# STM32F405RGT6.net
KiCad netlist of a schematic drawn in Altium Designer
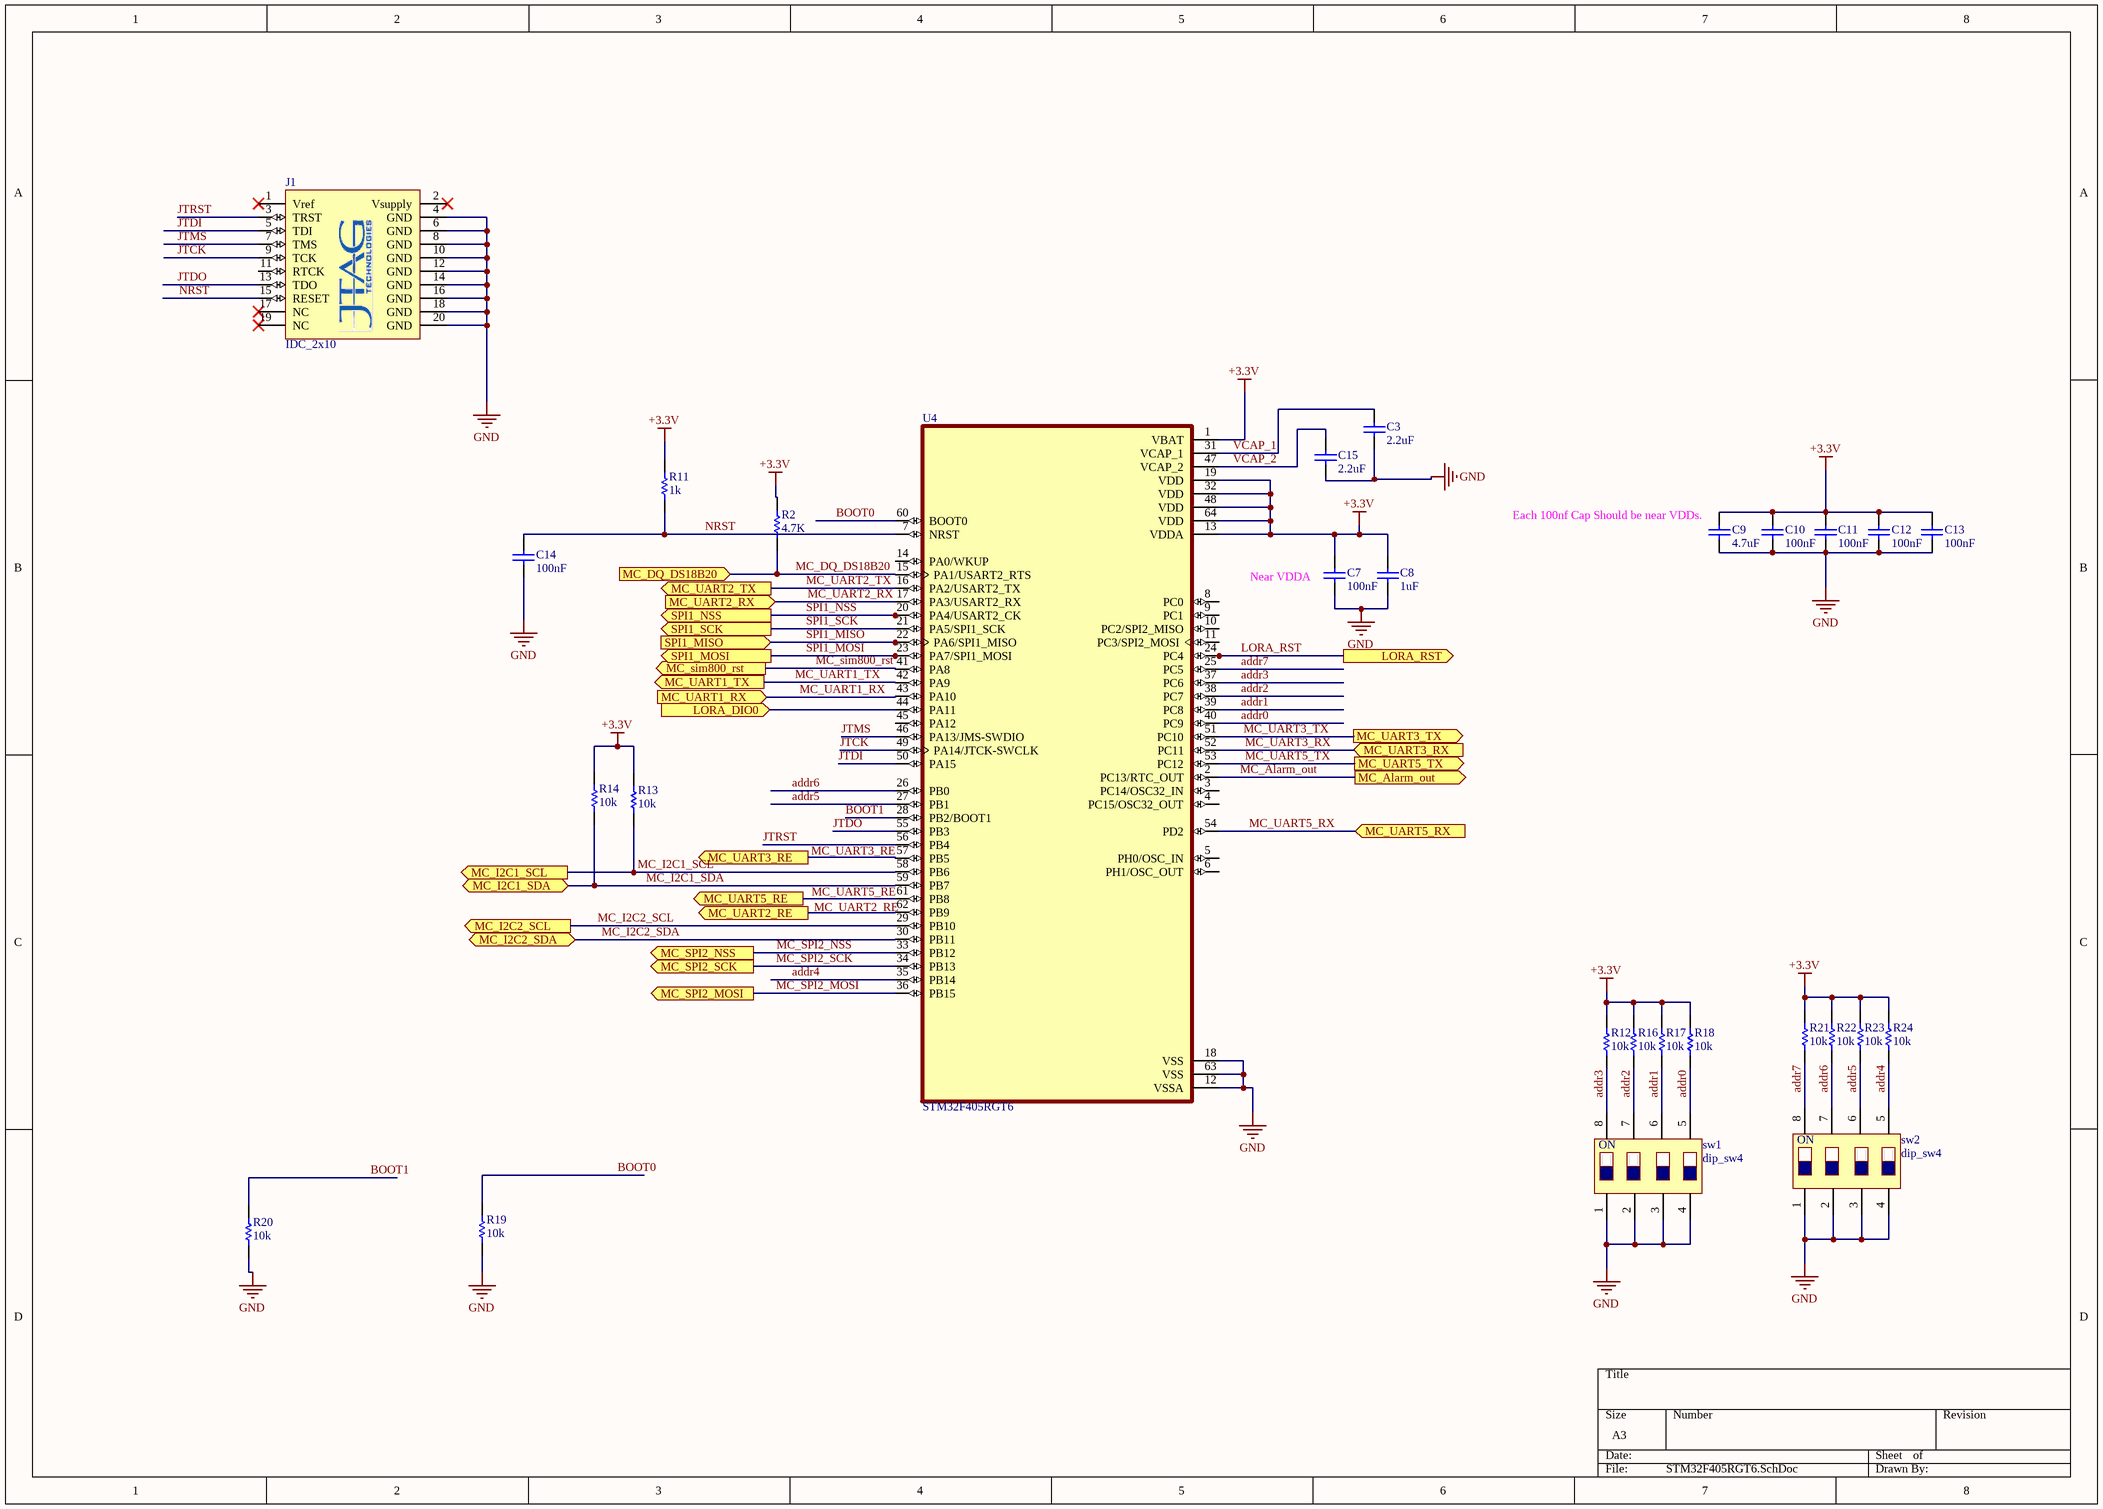
[diagram p0: STM32F405RGT6.SchDoc]

(export (version "E")
  (design (tool "Eeschema 10.0.6"))
  (components
    (comp (ref "C3")
      (value "2.2uF")
      (footprint "C-805")
      (description "Capacitor")
      (fields (field (name "Comment") "C-805") (field (name "PUBLISHER") "Altium Limited"))
      (libsource (lib "AfraLIB") (part "C-805"))
    )
    (comp (ref "C7")
      (value "100nF")
      (footprint "C-805")
      (description "Capacitor")
      (fields (field (name "Comment") "C-805") (field (name "PUBLISHER") "Altium Limited"))
      (libsource (lib "AfraLIB") (part "C-805"))
    )
    (comp (ref "C8")
      (value "1uF")
      (footprint "C-805")
      (description "Capacitor")
      (fields (field (name "Comment") "C-805") (field (name "PUBLISHER") "Altium Limited"))
      (libsource (lib "AfraLIB") (part "C-805"))
    )
    (comp (ref "C9")
      (value "4.7uF")
      (footprint "C-1206")
      (description "Capacitor")
      (fields (field (name "Comment") "C-1206") (field (name "PUBLISHER") "Altium Limited"))
      (libsource (lib "AfraLIB") (part "C-1206"))
    )
    (comp (ref "C10")
      (value "100nF")
      (footprint "C-603")
      (description "Capacitor")
      (fields (field (name "Comment") "C-603") (field (name "PUBLISHER") "Altium Limited"))
      (libsource (lib "AfraLIB") (part "C-603"))
    )
    (comp (ref "C11")
      (value "100nF")
      (footprint "C-603")
      (description "Capacitor")
      (fields (field (name "Comment") "C-603") (field (name "PUBLISHER") "Altium Limited"))
      (libsource (lib "AfraLIB") (part "C-603"))
    )
    (comp (ref "C12")
      (value "100nF")
      (footprint "C-603")
      (description "Capacitor")
      (fields (field (name "Comment") "C-603") (field (name "PUBLISHER") "Altium Limited"))
      (libsource (lib "AfraLIB") (part "C-603"))
    )
    (comp (ref "C13")
      (value "100nF")
      (footprint "C-603")
      (description "Capacitor")
      (fields (field (name "Comment") "C-603") (field (name "PUBLISHER") "Altium Limited"))
      (libsource (lib "AfraLIB") (part "C-603"))
    )
    (comp (ref "C14")
      (value "100nF")
      (footprint "C-805")
      (description "Capacitor")
      (fields (field (name "Comment") "C-805") (field (name "PUBLISHER") "Altium Limited"))
      (libsource (lib "AfraLIB") (part "C-805"))
    )
    (comp (ref "C15")
      (value "2.2uF")
      (footprint "C-805")
      (description "Capacitor")
      (fields (field (name "Comment") "C-805") (field (name "PUBLISHER") "Altium Limited"))
      (libsource (lib "AfraLIB") (part "C-805"))
    )
    (comp (ref "J1")
      (value "IDC_2x10")
      (footprint "IDC2.54-V20D")
      (description "20 Pin Standard JTAG Header For ARM JLINK")
      (fields (field (name "DESIGNER") "Eng. Saeid Jorablo") (field (name "PUBLISHER") "SJ UnLimited"))
      (libsource (lib "AfraLIB") (part "JTAG_JLINK"))
    )
    (comp (ref "R2")
      (value "4.7K")
      (footprint "R-805")
      (description "Resistor")
      (fields (field (name "Comment") "R-805"))
      (libsource (lib "AfraLIB") (part "R-805"))
    )
    (comp (ref "R11")
      (value "1k")
      (footprint "R-805")
      (description "Resistor")
      (fields (field (name "Comment") "R-805"))
      (libsource (lib "AfraLIB") (part "R-805"))
    )
    (comp (ref "R12")
      (value "10k")
      (footprint "R-805")
      (description "Resistor")
      (fields (field (name "Comment") "R-805"))
      (libsource (lib "AfraLIB") (part "R-805"))
    )
    (comp (ref "R13")
      (value "10k")
      (footprint "R-805")
      (description "Resistor")
      (fields (field (name "Comment") "R-805"))
      (libsource (lib "AfraLIB") (part "R-805"))
    )
    (comp (ref "R14")
      (value "10k")
      (footprint "R-805")
      (description "Resistor")
      (fields (field (name "Comment") "R-805"))
      (libsource (lib "AfraLIB") (part "R-805"))
    )
    (comp (ref "R16")
      (value "10k")
      (footprint "R-805")
      (description "Resistor")
      (fields (field (name "Comment") "R-805"))
      (libsource (lib "AfraLIB") (part "R-805"))
    )
    (comp (ref "R17")
      (value "10k")
      (footprint "R-805")
      (description "Resistor")
      (fields (field (name "Comment") "R-805"))
      (libsource (lib "AfraLIB") (part "R-805"))
    )
    (comp (ref "R18")
      (value "10k")
      (footprint "R-805")
      (description "Resistor")
      (fields (field (name "Comment") "R-805"))
      (libsource (lib "AfraLIB") (part "R-805"))
    )
    (comp (ref "R19")
      (value "10k")
      (footprint "R-805")
      (description "Resistor")
      (fields (field (name "Comment") "R-805"))
      (libsource (lib "AfraLIB") (part "R-805"))
    )
    (comp (ref "R20")
      (value "10k")
      (footprint "R-805")
      (description "Resistor")
      (fields (field (name "Comment") "R-805"))
      (libsource (lib "AfraLIB") (part "R-805"))
    )
    (comp (ref "R21")
      (value "10k")
      (footprint "R-805")
      (description "Resistor")
      (fields (field (name "Comment") "R-805"))
      (libsource (lib "AfraLIB") (part "R-805"))
    )
    (comp (ref "R22")
      (value "10k")
      (footprint "R-805")
      (description "Resistor")
      (fields (field (name "Comment") "R-805"))
      (libsource (lib "AfraLIB") (part "R-805"))
    )
    (comp (ref "R23")
      (value "10k")
      (footprint "R-805")
      (description "Resistor")
      (fields (field (name "Comment") "R-805"))
      (libsource (lib "AfraLIB") (part "R-805"))
    )
    (comp (ref "R24")
      (value "10k")
      (footprint "R-805")
      (description "Resistor")
      (fields (field (name "Comment") "R-805"))
      (libsource (lib "AfraLIB") (part "R-805"))
    )
    (comp (ref "sw1")
      (value "dip_sw4")
      (footprint "dipSW_4")
      (description "dip switch, 4-Pin")
      (fields (field (name "PUBLISHER") "Altium Limited"))
      (libsource (lib "AfraLIB") (part "dip_sw4"))
    )
    (comp (ref "sw2")
      (value "dip_sw4")
      (footprint "dipSW_4")
      (description "dip switch, 4-Pin")
      (fields (field (name "PUBLISHER") "Altium Limited"))
      (libsource (lib "AfraLIB") (part "dip_sw4"))
    )
    (comp (ref "U4")
      (value "STM32F405RGT6")
      (footprint "stm32f405rgt6")
      (description "ARMÂ® CortexÂ®-M4 STM32F4 Microcontroller IC 32-Bit 168MHz 1MB _1M x 8_ FLASH 64-LQFP _10x10_")
      (fields (field (name "MF") "STMicroelectronics") (field (name "DIGI-KEY_PART_NUMBER") "497-11767-ND"))
      (libsource (lib "AfraLIB") (part "STM32F405RGT6"))
    )
  )
  (nets
    (net (code "1") (name "+3.3V") (class "Default")
      (node (ref "C10") (pin "1") (pinfunction "1_1") (pintype "passive"))
      (node (ref "C11") (pin "1") (pinfunction "1_1") (pintype "passive"))
      (node (ref "C12") (pin "1") (pinfunction "1_1") (pintype "passive"))
      (node (ref "C13") (pin "1") (pinfunction "1_1") (pintype "passive"))
      (node (ref "C7") (pin "1") (pinfunction "1_1") (pintype "passive"))
      (node (ref "C8") (pin "2") (pinfunction "2_2") (pintype "passive"))
      (node (ref "C9") (pin "2") (pinfunction "2_2") (pintype "passive"))
      (node (ref "R11") (pin "2") (pinfunction "2_2") (pintype "passive"))
      (node (ref "R12") (pin "2") (pinfunction "2_2") (pintype "passive"))
      (node (ref "R13") (pin "2") (pinfunction "2_2") (pintype "passive"))
      (node (ref "R14") (pin "2") (pinfunction "2_2") (pintype "passive"))
      (node (ref "R16") (pin "2") (pinfunction "2_2") (pintype "passive"))
      (node (ref "R17") (pin "2") (pinfunction "2_2") (pintype "passive"))
      (node (ref "R18") (pin "2") (pinfunction "2_2") (pintype "passive"))
      (node (ref "R2") (pin "2") (pinfunction "2_2") (pintype "passive"))
      (node (ref "R21") (pin "2") (pinfunction "2_2") (pintype "passive"))
      (node (ref "R22") (pin "2") (pinfunction "2_2") (pintype "passive"))
      (node (ref "R23") (pin "2") (pinfunction "2_2") (pintype "passive"))
      (node (ref "R24") (pin "2") (pinfunction "2_2") (pintype "passive"))
      (node (ref "U4") (pin "1") (pinfunction "VBAT_1") (pintype "power_in"))
      (node (ref "U4") (pin "13") (pinfunction "VDDA_13") (pintype "power_in"))
      (node (ref "U4") (pin "19") (pinfunction "VDD_19") (pintype "power_in"))
      (node (ref "U4") (pin "32") (pinfunction "VDD_32") (pintype "power_in"))
      (node (ref "U4") (pin "48") (pinfunction "VDD_48") (pintype "power_in"))
      (node (ref "U4") (pin "64") (pinfunction "VDD_64") (pintype "power_in"))
    )
    (net (code "2") (name "/BOOT0") (class "Default")
      (node (ref "R19") (pin "2") (pinfunction "2_2") (pintype "passive"))
      (node (ref "U4") (pin "60") (pinfunction "BOOT0_60") (pintype "bidirectional"))
    )
    (net (code "3") (name "/BOOT1") (class "Default")
      (node (ref "R20") (pin "1") (pinfunction "1_1") (pintype "passive"))
      (node (ref "U4") (pin "28") (pinfunction "PB2/BOOT1_28") (pintype "bidirectional"))
    )
    (net (code "4") (name "/JTCK") (class "Default")
      (node (ref "J1") (pin "9") (pinfunction "TCK_9") (pintype "bidirectional"))
      (node (ref "U4") (pin "49") (pinfunction "PA14/JTCK-SWCLK_49") (pintype "bidirectional"))
    )
    (net (code "5") (name "/JTDI") (class "Default")
      (node (ref "J1") (pin "5") (pinfunction "TDI_5") (pintype "bidirectional"))
      (node (ref "U4") (pin "50") (pinfunction "PA15_50") (pintype "bidirectional"))
    )
    (net (code "6") (name "/JTDO") (class "Default")
      (node (ref "J1") (pin "13") (pinfunction "TDO_13") (pintype "bidirectional"))
      (node (ref "U4") (pin "55") (pinfunction "PB3_55") (pintype "bidirectional"))
    )
    (net (code "7") (name "/JTMS") (class "Default")
      (node (ref "J1") (pin "7") (pinfunction "TMS_7") (pintype "bidirectional"))
      (node (ref "U4") (pin "46") (pinfunction "PA13/JMS-SWDIO_46") (pintype "bidirectional"))
    )
    (net (code "8") (name "/JTRST") (class "Default")
      (node (ref "J1") (pin "3") (pinfunction "TRST_3") (pintype "bidirectional"))
      (node (ref "U4") (pin "56") (pinfunction "PB4_56") (pintype "bidirectional"))
    )
    (net (code "9") (name "/LORA_DIO0") (class "Default")
      (node (ref "U4") (pin "44") (pinfunction "PA11_44") (pintype "bidirectional"))
    )
    (net (code "10") (name "/LORA_RST") (class "Default")
      (node (ref "U4") (pin "24") (pinfunction "PC4_24") (pintype "bidirectional"))
    )
    (net (code "11") (name "/MC_Alarm_out") (class "Default")
      (node (ref "U4") (pin "2") (pinfunction "PC13/RTC_OUT_2") (pintype "bidirectional"))
    )
    (net (code "12") (name "/MC_DQ_DS18B20") (class "Default")
      (node (ref "R2") (pin "1") (pinfunction "1_1") (pintype "passive"))
      (node (ref "U4") (pin "15") (pinfunction "PA1/USART2_RTS_15") (pintype "bidirectional"))
    )
    (net (code "13") (name "/MC_I2C1_SCL") (class "Default")
      (node (ref "R13") (pin "1") (pinfunction "1_1") (pintype "passive"))
      (node (ref "U4") (pin "58") (pinfunction "PB6_58") (pintype "bidirectional"))
    )
    (net (code "14") (name "/MC_I2C1_SDA") (class "Default")
      (node (ref "R14") (pin "1") (pinfunction "1_1") (pintype "passive"))
      (node (ref "U4") (pin "59") (pinfunction "PB7_59") (pintype "bidirectional"))
    )
    (net (code "15") (name "/MC_I2C2_SCL") (class "Default")
      (node (ref "U4") (pin "29") (pinfunction "PB10_29") (pintype "bidirectional"))
    )
    (net (code "16") (name "/MC_I2C2_SDA") (class "Default")
      (node (ref "U4") (pin "30") (pinfunction "PB11_30") (pintype "bidirectional"))
    )
    (net (code "17") (name "/MC_SPI2_MOSI") (class "Default")
      (node (ref "U4") (pin "36") (pinfunction "PB15_36") (pintype "bidirectional"))
    )
    (net (code "18") (name "/MC_SPI2_NSS") (class "Default")
      (node (ref "U4") (pin "33") (pinfunction "PB12_33") (pintype "bidirectional"))
    )
    (net (code "19") (name "/MC_SPI2_SCK") (class "Default")
      (node (ref "U4") (pin "34") (pinfunction "PB13_34") (pintype "bidirectional"))
    )
    (net (code "20") (name "/MC_UART1_RX") (class "Default")
      (node (ref "U4") (pin "43") (pinfunction "PA10_43") (pintype "bidirectional"))
    )
    (net (code "21") (name "/MC_UART1_TX") (class "Default")
      (node (ref "U4") (pin "42") (pinfunction "PA9_42") (pintype "bidirectional"))
    )
    (net (code "22") (name "/MC_UART2_RE") (class "Default")
      (node (ref "U4") (pin "62") (pinfunction "PB9_62") (pintype "bidirectional"))
    )
    (net (code "23") (name "/MC_UART2_RX") (class "Default")
      (node (ref "U4") (pin "17") (pinfunction "PA3/USART2_RX_17") (pintype "bidirectional"))
    )
    (net (code "24") (name "/MC_UART2_TX") (class "Default")
      (node (ref "U4") (pin "16") (pinfunction "PA2/USART2_TX_16") (pintype "bidirectional"))
    )
    (net (code "25") (name "/MC_UART3_RE") (class "Default")
      (node (ref "U4") (pin "57") (pinfunction "PB5_57") (pintype "bidirectional"))
    )
    (net (code "26") (name "/MC_UART3_RX") (class "Default")
      (node (ref "U4") (pin "52") (pinfunction "PC11_52") (pintype "bidirectional"))
    )
    (net (code "27") (name "/MC_UART3_TX") (class "Default")
      (node (ref "U4") (pin "51") (pinfunction "PC10_51") (pintype "bidirectional"))
    )
    (net (code "28") (name "/MC_UART5_RE") (class "Default")
      (node (ref "U4") (pin "61") (pinfunction "PB8_61") (pintype "bidirectional"))
    )
    (net (code "29") (name "/MC_UART5_RX") (class "Default")
      (node (ref "U4") (pin "54") (pinfunction "PD2_54") (pintype "bidirectional"))
    )
    (net (code "30") (name "/MC_UART5_TX") (class "Default")
      (node (ref "U4") (pin "53") (pinfunction "PC12_53") (pintype "bidirectional"))
    )
    (net (code "31") (name "/MC_sim800_rst") (class "Default")
      (node (ref "U4") (pin "41") (pinfunction "PA8_41") (pintype "bidirectional"))
    )
    (net (code "32") (name "/NRST") (class "Default")
      (node (ref "C14") (pin "1") (pinfunction "1_1") (pintype "passive"))
      (node (ref "J1") (pin "15") (pinfunction "RESET_15") (pintype "bidirectional"))
      (node (ref "R11") (pin "1") (pinfunction "1_1") (pintype "passive"))
      (node (ref "U4") (pin "7") (pinfunction "NRST_7") (pintype "bidirectional"))
    )
    (net (code "33") (name "/SPI1_MISO") (class "Default")
      (node (ref "U4") (pin "22") (pinfunction "PA6/SPI1_MISO_22") (pintype "bidirectional"))
    )
    (net (code "34") (name "/SPI1_MOSI") (class "Default")
      (node (ref "U4") (pin "23") (pinfunction "PA7/SPI1_MOSI_23") (pintype "bidirectional"))
    )
    (net (code "35") (name "/SPI1_NSS") (class "Default")
      (node (ref "U4") (pin "20") (pinfunction "PA4/USART2_CK_20") (pintype "bidirectional"))
    )
    (net (code "36") (name "/SPI1_SCK") (class "Default")
      (node (ref "U4") (pin "21") (pinfunction "PA5/SPI1_SCK_21") (pintype "bidirectional"))
    )
    (net (code "37") (name "/VCAP_1") (class "Default")
      (node (ref "C3") (pin "2") (pinfunction "2_2") (pintype "passive"))
      (node (ref "U4") (pin "31") (pinfunction "VCAP_1_31") (pintype "power_in"))
    )
    (net (code "38") (name "/VCAP_2") (class "Default")
      (node (ref "C15") (pin "2") (pinfunction "2_2") (pintype "passive"))
      (node (ref "U4") (pin "47") (pinfunction "VCAP_2_47") (pintype "power_in"))
    )
    (net (code "39") (name "/addr0") (class "Default")
      (node (ref "R18") (pin "1") (pinfunction "1_1") (pintype "passive"))
      (node (ref "U4") (pin "40") (pinfunction "PC9_40") (pintype "bidirectional"))
      (node (ref "sw1") (pin "5") (pinfunction "5_5") (pintype "passive"))
    )
    (net (code "40") (name "/addr1") (class "Default")
      (node (ref "R17") (pin "1") (pinfunction "1_1") (pintype "passive"))
      (node (ref "U4") (pin "39") (pinfunction "PC8_39") (pintype "bidirectional"))
      (node (ref "sw1") (pin "6") (pinfunction "6_6") (pintype "passive"))
    )
    (net (code "41") (name "/addr2") (class "Default")
      (node (ref "R16") (pin "1") (pinfunction "1_1") (pintype "passive"))
      (node (ref "U4") (pin "38") (pinfunction "PC7_38") (pintype "bidirectional"))
      (node (ref "sw1") (pin "7") (pinfunction "7_7") (pintype "passive"))
    )
    (net (code "42") (name "/addr3") (class "Default")
      (node (ref "R12") (pin "1") (pinfunction "1_1") (pintype "passive"))
      (node (ref "U4") (pin "37") (pinfunction "PC6_37") (pintype "bidirectional"))
      (node (ref "sw1") (pin "8") (pintype "passive"))
    )
    (net (code "43") (name "/addr4") (class "Default")
      (node (ref "R24") (pin "1") (pinfunction "1_1") (pintype "passive"))
      (node (ref "U4") (pin "35") (pinfunction "PB14_35") (pintype "bidirectional"))
      (node (ref "sw2") (pin "5") (pinfunction "5_5") (pintype "passive"))
    )
    (net (code "44") (name "/addr5") (class "Default")
      (node (ref "R23") (pin "1") (pinfunction "1_1") (pintype "passive"))
      (node (ref "U4") (pin "27") (pinfunction "PB1_27") (pintype "bidirectional"))
      (node (ref "sw2") (pin "6") (pinfunction "6_6") (pintype "passive"))
    )
    (net (code "45") (name "/addr6") (class "Default")
      (node (ref "R22") (pin "1") (pinfunction "1_1") (pintype "passive"))
      (node (ref "U4") (pin "26") (pinfunction "PB0_26") (pintype "bidirectional"))
      (node (ref "sw2") (pin "7") (pinfunction "7_7") (pintype "passive"))
    )
    (net (code "46") (name "/addr7") (class "Default")
      (node (ref "R21") (pin "1") (pinfunction "1_1") (pintype "passive"))
      (node (ref "U4") (pin "25") (pinfunction "PC5_25") (pintype "bidirectional"))
      (node (ref "sw2") (pin "8") (pintype "passive"))
    )
    (net (code "47") (name "GND") (class "Default")
      (node (ref "C10") (pin "2") (pinfunction "2_2") (pintype "passive"))
      (node (ref "C11") (pin "2") (pinfunction "2_2") (pintype "passive"))
      (node (ref "C12") (pin "2") (pinfunction "2_2") (pintype "passive"))
      (node (ref "C13") (pin "2") (pinfunction "2_2") (pintype "passive"))
      (node (ref "C14") (pin "2") (pinfunction "2_2") (pintype "passive"))
      (node (ref "C15") (pin "1") (pinfunction "1_1") (pintype "passive"))
      (node (ref "C3") (pin "1") (pinfunction "1_1") (pintype "passive"))
      (node (ref "C7") (pin "2") (pinfunction "2_2") (pintype "passive"))
      (node (ref "C8") (pin "1") (pinfunction "1_1") (pintype "passive"))
      (node (ref "C9") (pin "1") (pinfunction "1_1") (pintype "passive"))
      (node (ref "J1") (pin "10") (pinfunction "GND_10") (pintype "power_in"))
      (node (ref "J1") (pin "12") (pinfunction "GND_12") (pintype "power_in"))
      (node (ref "J1") (pin "14") (pinfunction "GND_14") (pintype "power_in"))
      (node (ref "J1") (pin "16") (pinfunction "GND_16") (pintype "power_in"))
      (node (ref "J1") (pin "18") (pinfunction "GND_18") (pintype "power_in"))
      (node (ref "J1") (pin "20") (pinfunction "GND_20") (pintype "power_in"))
      (node (ref "J1") (pin "4") (pinfunction "GND_4") (pintype "power_in"))
      (node (ref "J1") (pin "6") (pinfunction "GND_6") (pintype "power_in"))
      (node (ref "J1") (pin "8") (pinfunction "GND_8") (pintype "power_in"))
      (node (ref "R19") (pin "1") (pinfunction "1_1") (pintype "passive"))
      (node (ref "R20") (pin "2") (pinfunction "2_2") (pintype "passive"))
      (node (ref "U4") (pin "12") (pinfunction "VSSA_12") (pintype "power_in"))
      (node (ref "U4") (pin "18") (pinfunction "VSS_18") (pintype "power_in"))
      (node (ref "U4") (pin "63") (pinfunction "VSS_63") (pintype "power_in"))
      (node (ref "sw1") (pin "1") (pinfunction "1_1") (pintype "passive"))
      (node (ref "sw1") (pin "2") (pinfunction "2_2") (pintype "passive"))
      (node (ref "sw1") (pin "3") (pinfunction "3_3") (pintype "passive"))
      (node (ref "sw1") (pin "4") (pinfunction "4_4") (pintype "passive"))
      (node (ref "sw2") (pin "1") (pinfunction "1_1") (pintype "passive"))
      (node (ref "sw2") (pin "2") (pinfunction "2_2") (pintype "passive"))
      (node (ref "sw2") (pin "3") (pinfunction "3_3") (pintype "passive"))
      (node (ref "sw2") (pin "4") (pinfunction "4_4") (pintype "passive"))
    )
    (net (code "48") (name "unconnected-(J1-NC-Pad17)") (class "Default")
      (node (ref "J1") (pin "17") (pinfunction "NC_17") (pintype "passive+no_connect"))
    )
    (net (code "49") (name "unconnected-(J1-NC-Pad19)") (class "Default")
      (node (ref "J1") (pin "19") (pinfunction "NC_19") (pintype "passive+no_connect"))
    )
    (net (code "50") (name "unconnected-(J1-RTCK-Pad11)") (class "Default")
      (node (ref "J1") (pin "11") (pinfunction "RTCK_11") (pintype "bidirectional"))
    )
    (net (code "51") (name "unconnected-(J1-Vref-Pad1)") (class "Default")
      (node (ref "J1") (pin "1") (pinfunction "Vref_1") (pintype "power_in+no_connect"))
    )
    (net (code "52") (name "unconnected-(J1-Vsupply-Pad2)") (class "Default")
      (node (ref "J1") (pin "2") (pinfunction "Vsupply_2") (pintype "power_in+no_connect"))
    )
    (net (code "53") (name "unconnected-(U4-PA0{slash}WKUP-Pad14)") (class "Default")
      (node (ref "U4") (pin "14") (pinfunction "PA0/WKUP_14") (pintype "bidirectional"))
    )
    (net (code "54") (name "unconnected-(U4-PA12-Pad45)") (class "Default")
      (node (ref "U4") (pin "45") (pinfunction "PA12_45") (pintype "bidirectional"))
    )
    (net (code "55") (name "unconnected-(U4-PC0-Pad8)") (class "Default")
      (node (ref "U4") (pin "8") (pinfunction "PC0_8") (pintype "bidirectional"))
    )
    (net (code "56") (name "unconnected-(U4-PC1-Pad9)") (class "Default")
      (node (ref "U4") (pin "9") (pinfunction "PC1_9") (pintype "bidirectional"))
    )
    (net (code "57") (name "unconnected-(U4-PC2{slash}SPI2_MISO-Pad10)") (class "Default")
      (node (ref "U4") (pin "10") (pinfunction "PC2/SPI2_MISO_10") (pintype "bidirectional"))
    )
    (net (code "58") (name "unconnected-(U4-PC3{slash}SPI2_MOSI-Pad11)") (class "Default")
      (node (ref "U4") (pin "11") (pinfunction "PC3/SPI2_MOSI_11") (pintype "bidirectional"))
    )
    (net (code "59") (name "unconnected-(U4-PC14{slash}OSC32_IN-Pad3)") (class "Default")
      (node (ref "U4") (pin "3") (pinfunction "PC14/OSC32_IN_3") (pintype "bidirectional"))
    )
    (net (code "60") (name "unconnected-(U4-PC15{slash}OSC32_OUT-Pad4)") (class "Default")
      (node (ref "U4") (pin "4") (pinfunction "PC15/OSC32_OUT_4") (pintype "bidirectional"))
    )
    (net (code "61") (name "unconnected-(U4-PH0{slash}OSC_IN-Pad5)") (class "Default")
      (node (ref "U4") (pin "5") (pinfunction "PH0/OSC_IN_5") (pintype "bidirectional"))
    )
    (net (code "62") (name "unconnected-(U4-PH1{slash}OSC_OUT-Pad6)") (class "Default")
      (node (ref "U4") (pin "6") (pinfunction "PH1/OSC_OUT_6") (pintype "bidirectional"))
    )
  )
)
